# lab5.net
KiCad netlist of a schematic drawn in EAGLE
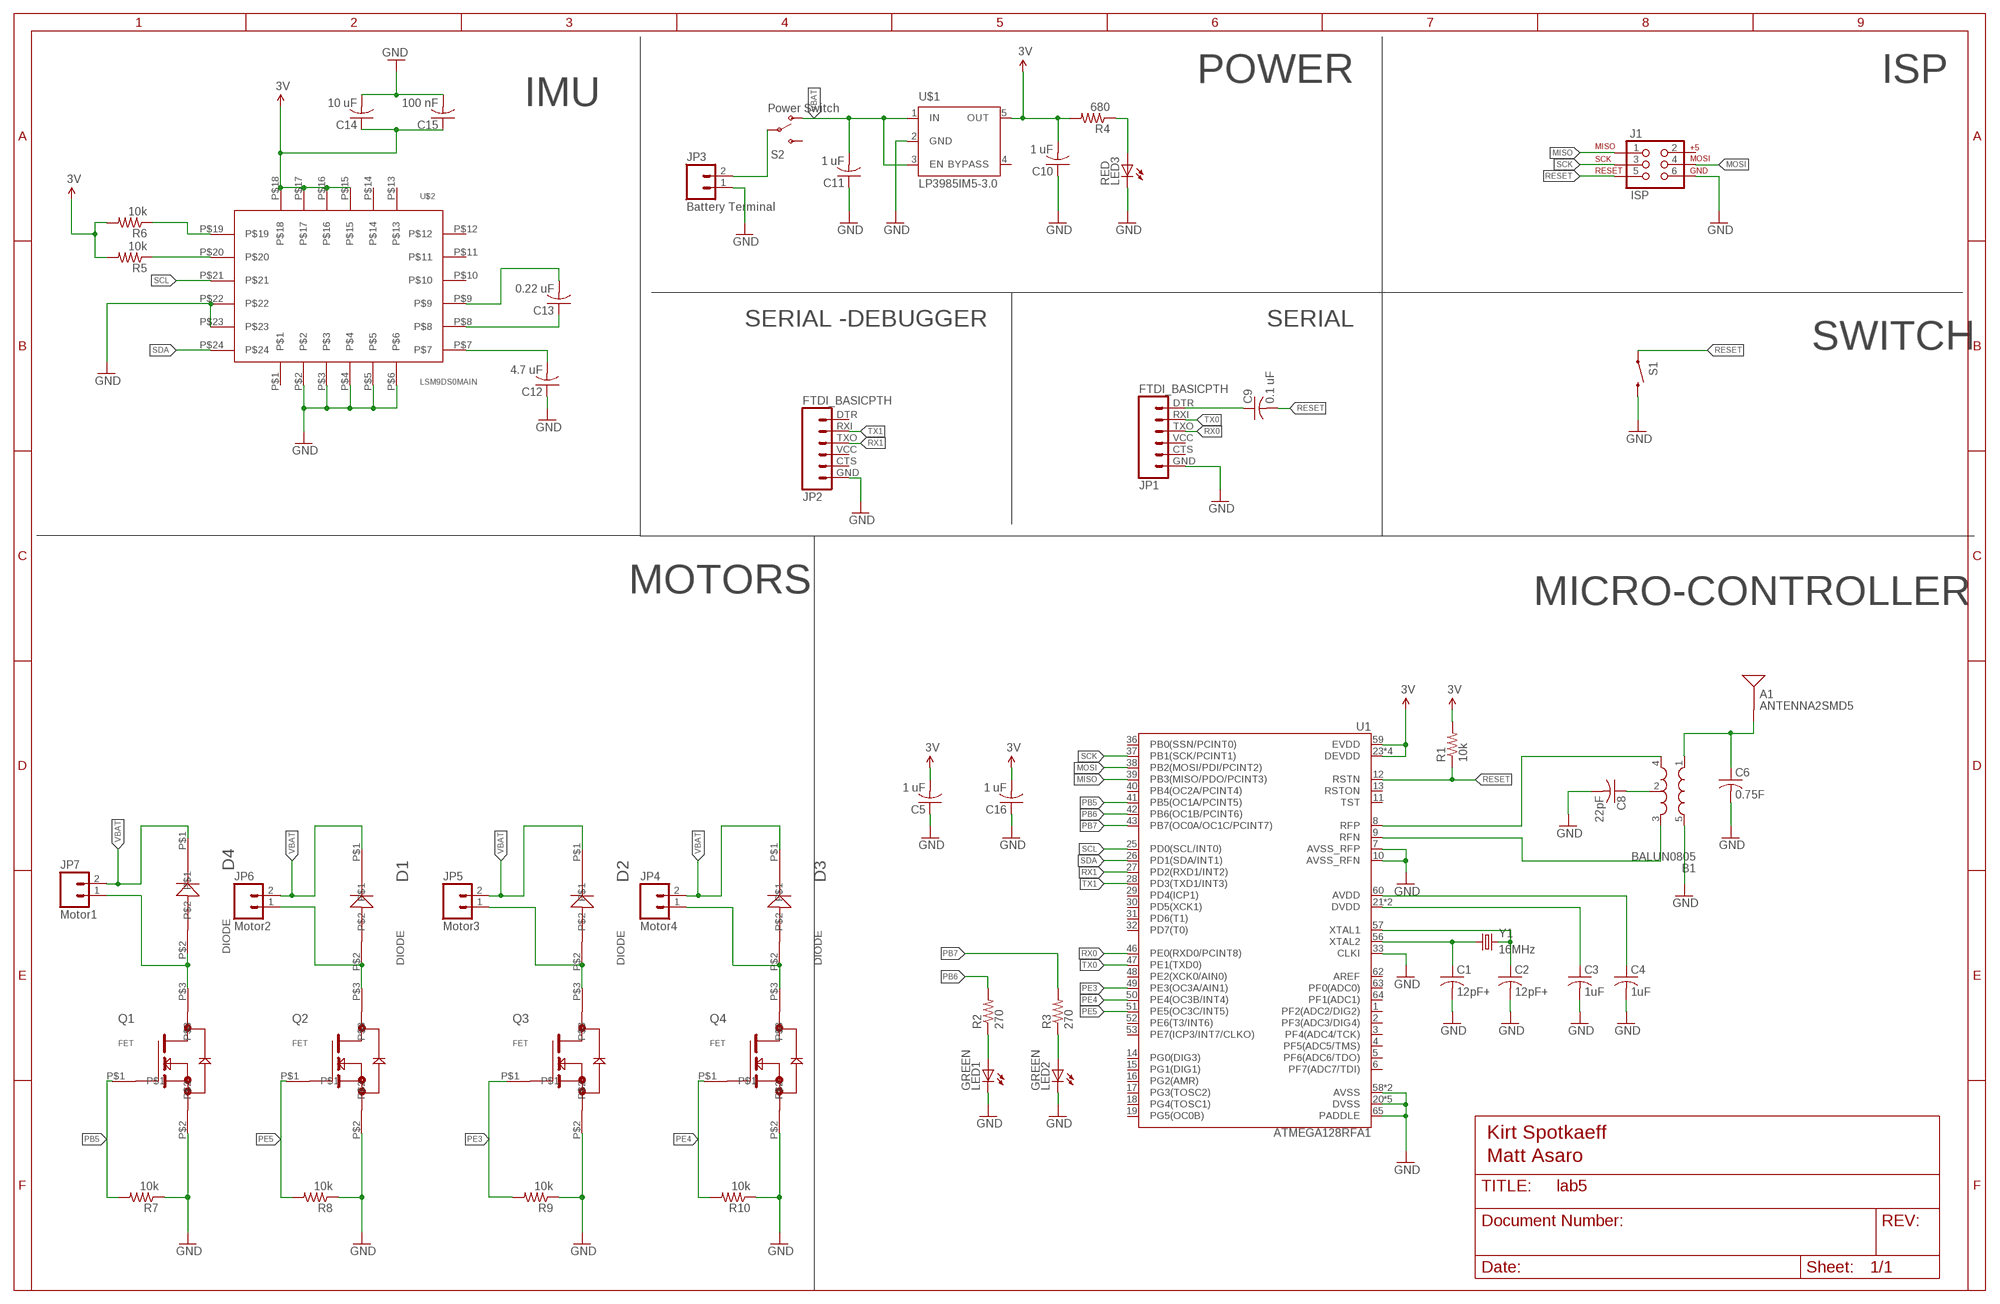
[diagram p0: schematic, sheet 1]

(export (version "E")
  (design (tool "Eeschema 10.0.6"))
  (components
    (comp (ref "A1")
      (value "ANTENNA2SMD5")
      (footprint "eagle-import:ANTENNA-CHIP5")
      (libsource (lib "eagle-import") (part "ANTENNA2SMD5"))
    )
    (comp (ref "B1")
      (value "BALUN0805")
      (footprint "eagle-import:BALUN")
      (libsource (lib "eagle-import") (part "BALUN0805"))
    )
    (comp (ref "C1")
      (value "12pF+")
      (footprint "eagle-import:C0805")
      (libsource (lib "eagle-import") (part "C-USC0805"))
    )
    (comp (ref "C2")
      (value "12pF+")
      (footprint "eagle-import:C0805")
      (libsource (lib "eagle-import") (part "C-USC0805"))
    )
    (comp (ref "C3")
      (value "1uF")
      (footprint "eagle-import:C0805")
      (libsource (lib "eagle-import") (part "C-USC0805"))
    )
    (comp (ref "C4")
      (value "1uF")
      (footprint "eagle-import:C0805")
      (libsource (lib "eagle-import") (part "C-USC0805"))
    )
    (comp (ref "C5")
      (value "1 uF")
      (footprint "eagle-import:C0805")
      (libsource (lib "eagle-import") (part "C-USC0805"))
    )
    (comp (ref "C6")
      (value "0.75F")
      (footprint "eagle-import:C0805")
      (libsource (lib "eagle-import") (part "C-USC0805"))
    )
    (comp (ref "C8")
      (value "22pF")
      (footprint "eagle-import:C0805")
      (libsource (lib "eagle-import") (part "C-USC0805"))
    )
    (comp (ref "C9")
      (value "0.1 uF")
      (footprint "eagle-import:C0805")
      (libsource (lib "eagle-import") (part "C-USC0805"))
    )
    (comp (ref "C10")
      (value "1 uF")
      (footprint "eagle-import:C0805")
      (libsource (lib "eagle-import") (part "C-USC0805"))
    )
    (comp (ref "C11")
      (value "1 uF")
      (footprint "eagle-import:C0805")
      (libsource (lib "eagle-import") (part "C-USC0805"))
    )
    (comp (ref "C12")
      (value "4.7 uF")
      (footprint "eagle-import:C0805")
      (libsource (lib "eagle-import") (part "C-USC0805"))
    )
    (comp (ref "C13")
      (value "0.22 uF")
      (footprint "eagle-import:C0805")
      (libsource (lib "eagle-import") (part "C-USC0805"))
    )
    (comp (ref "C14")
      (value "10 uF")
      (footprint "eagle-import:C0805")
      (libsource (lib "eagle-import") (part "C-USC0805"))
    )
    (comp (ref "C15")
      (value "100 nF")
      (footprint "eagle-import:C0805")
      (libsource (lib "eagle-import") (part "C-USC0805"))
    )
    (comp (ref "C16")
      (value "1 uF")
      (footprint "eagle-import:C0805")
      (libsource (lib "eagle-import") (part "C-USC0805"))
    )
    (comp (ref "D1")
      (value "DIODE")
      (footprint "eagle-import:DIODE")
      (fields (field (name "CREATOR") "Kirt Spotkaeff"))
      (libsource (lib "eagle-import") (part "DIODE"))
    )
    (comp (ref "D2")
      (value "DIODE")
      (footprint "eagle-import:DIODE")
      (fields (field (name "CREATOR") "Kirt Spotkaeff"))
      (libsource (lib "eagle-import") (part "DIODE"))
    )
    (comp (ref "D3")
      (value "DIODE")
      (footprint "eagle-import:DIODE")
      (fields (field (name "CREATOR") "Kirt Spotkaeff"))
      (libsource (lib "eagle-import") (part "DIODE"))
    )
    (comp (ref "D4")
      (value "DIODE")
      (footprint "eagle-import:DIODE")
      (fields (field (name "CREATOR") "Kirt Spotkaeff"))
      (libsource (lib "eagle-import") (part "DIODE"))
    )
    (comp (ref "J1")
      (value "ISP")
      (footprint "eagle-import:2X3-NS")
      (libsource (lib "eagle-import") (part "AVR_SPI_PRG_6NS"))
    )
    (comp (ref "JP1")
      (value "FTDI_BASICPTH")
      (footprint "eagle-import:FTDI_BASIC")
      (libsource (lib "eagle-import") (part "FTDI_BASICPTH"))
    )
    (comp (ref "JP2")
      (value "FTDI_BASICPTH")
      (footprint "eagle-import:FTDI_BASIC")
      (libsource (lib "eagle-import") (part "FTDI_BASICPTH"))
    )
    (comp (ref "JP3")
      (value "Battery Terminal")
      (footprint "eagle-import:1X02")
      (libsource (lib "eagle-import") (part "M02PTH"))
    )
    (comp (ref "JP4")
      (value "Motor4")
      (footprint "eagle-import:1X02")
      (libsource (lib "eagle-import") (part "M02PTH"))
    )
    (comp (ref "JP5")
      (value "Motor3")
      (footprint "eagle-import:1X02")
      (libsource (lib "eagle-import") (part "M02PTH"))
    )
    (comp (ref "JP6")
      (value "Motor2")
      (footprint "eagle-import:1X02")
      (libsource (lib "eagle-import") (part "M02PTH"))
    )
    (comp (ref "JP7")
      (value "Motor1")
      (footprint "eagle-import:1X02")
      (libsource (lib "eagle-import") (part "M02PTH"))
    )
    (comp (ref "LED1")
      (value "GREEN")
      (footprint "eagle-import:CHIP-LED0805")
      (libsource (lib "eagle-import") (part "LEDCHIP-LED0805"))
    )
    (comp (ref "LED2")
      (value "GREEN")
      (footprint "eagle-import:CHIP-LED0805")
      (libsource (lib "eagle-import") (part "LEDCHIP-LED0805"))
    )
    (comp (ref "LED3")
      (value "RED")
      (footprint "eagle-import:CHIP-LED0805")
      (libsource (lib "eagle-import") (part "LEDCHIP-LED0805"))
    )
    (comp (ref "Q1")
      (value "FET")
      (footprint "eagle-import:FET")
      (fields (field (name "CREATOR") "Kirt Spotkaeff"))
      (libsource (lib "eagle-import") (part "FET"))
    )
    (comp (ref "Q2")
      (value "FET")
      (footprint "eagle-import:FET")
      (fields (field (name "CREATOR") "Kirt Spotkaeff"))
      (libsource (lib "eagle-import") (part "FET"))
    )
    (comp (ref "Q3")
      (value "FET")
      (footprint "eagle-import:FET")
      (fields (field (name "CREATOR") "Kirt Spotkaeff"))
      (libsource (lib "eagle-import") (part "FET"))
    )
    (comp (ref "Q4")
      (value "FET")
      (footprint "eagle-import:FET")
      (fields (field (name "CREATOR") "Kirt Spotkaeff"))
      (libsource (lib "eagle-import") (part "FET"))
    )
    (comp (ref "R1")
      (value "10k")
      (footprint "eagle-import:R0805")
      (libsource (lib "eagle-import") (part "R-US_R0805"))
    )
    (comp (ref "R2")
      (value "270")
      (footprint "eagle-import:R0805")
      (libsource (lib "eagle-import") (part "R-US_R0805"))
    )
    (comp (ref "R3")
      (value "270")
      (footprint "eagle-import:R0805")
      (libsource (lib "eagle-import") (part "R-US_R0805"))
    )
    (comp (ref "R4")
      (value "680")
      (footprint "eagle-import:R0805")
      (libsource (lib "eagle-import") (part "R-US_R0805"))
    )
    (comp (ref "R5")
      (value "10k")
      (footprint "eagle-import:R0805")
      (libsource (lib "eagle-import") (part "R-US_R0805"))
    )
    (comp (ref "R6")
      (value "10k")
      (footprint "eagle-import:R0805")
      (libsource (lib "eagle-import") (part "R-US_R0805"))
    )
    (comp (ref "R7")
      (value "10k")
      (footprint "eagle-import:R0805")
      (libsource (lib "eagle-import") (part "R-US_R0805"))
    )
    (comp (ref "R8")
      (value "10k")
      (footprint "eagle-import:R0805")
      (libsource (lib "eagle-import") (part "R-US_R0805"))
    )
    (comp (ref "R9")
      (value "10k")
      (footprint "eagle-import:R0805")
      (libsource (lib "eagle-import") (part "R-US_R0805"))
    )
    (comp (ref "R10")
      (value "10k")
      (footprint "eagle-import:R0805")
      (libsource (lib "eagle-import") (part "R-US_R0805"))
    )
    (comp (ref "S1")
      (value "SWITCH-MOMENTARY-2SMD")
      (footprint "eagle-import:TACTILE_SWITCH_SMD")
      (libsource (lib "eagle-import") (part "SWITCH-MOMENTARY-2SMD"))
    )
    (comp (ref "S2")
      (value "Power Switch")
      (footprint "eagle-import:SWITCH-SPDT")
      (libsource (lib "eagle-import") (part "SWITCH-SPDTPTH"))
    )
    (comp (ref "U$1")
      (value "LP3985IM5-3.0")
      (footprint "eagle-import:SOT23-DBV")
      (libsource (lib "eagle-import") (part "LP3985IM5-3.0"))
    )
    (comp (ref "U$2")
      (value "LSM9DS0MAIN")
      (footprint "eagle-import:LSM9DS0")
      (libsource (lib "eagle-import") (part "LSM9DS0MAIN"))
    )
    (comp (ref "U1")
      (value "ATMEGA128RFA1")
      (footprint "eagle-import:QFN-64")
      (libsource (lib "eagle-import") (part "ATMEGA128RFA1"))
    )
    (comp (ref "Y1")
      (value "16MHz")
      (footprint "eagle-import:CRYSTAL-SMD-5X3")
      (libsource (lib "eagle-import") (part "CRYSTAL5X3"))
    )
  )
  (nets
    (net (code "1") (name "3V") (class "Default")
      (node (ref "C10") (pin "2") (pinfunction "2_2") (pintype "passive"))
      (node (ref "C14") (pin "1") (pinfunction "1_1") (pintype "passive"))
      (node (ref "C15") (pin "1") (pinfunction "1_1") (pintype "passive"))
      (node (ref "C16") (pin "2") (pinfunction "2_2") (pintype "passive"))
      (node (ref "C5") (pin "2") (pinfunction "2_2") (pintype "passive"))
      (node (ref "R1") (pin "2") (pinfunction "2_2") (pintype "passive"))
      (node (ref "R4") (pin "2") (pinfunction "2_2") (pintype "passive"))
      (node (ref "R5") (pin "2") (pinfunction "2_2") (pintype "passive"))
      (node (ref "R6") (pin "2") (pinfunction "2_2") (pintype "passive"))
      (node (ref "U$1") (pin "5") (pinfunction "OUT_5") (pintype "passive"))
      (node (ref "U$2") (pin "P$15") (pinfunction "P$15_P$15") (pintype "bidirectional"))
      (node (ref "U$2") (pin "P$16") (pinfunction "P$16_P$16") (pintype "bidirectional"))
      (node (ref "U$2") (pin "P$17") (pinfunction "P$17_P$17") (pintype "bidirectional"))
      (node (ref "U$2") (pin "P$18") (pinfunction "P$18_P$18") (pintype "bidirectional"))
      (node (ref "U1") (pin "23") (pinfunction "DEVDD_23") (pintype "bidirectional"))
      (node (ref "U1") (pin "34") (pinfunction "DEVDD_34") (pintype "bidirectional"))
      (node (ref "U1") (pin "44") (pinfunction "DEVDD_44") (pintype "bidirectional"))
      (node (ref "U1") (pin "54") (pinfunction "DEVDD_54") (pintype "bidirectional"))
      (node (ref "U1") (pin "59") (pinfunction "EVDD_59") (pintype "bidirectional"))
    )
    (net (code "2") (name "GND") (class "Default")
      (node (ref "B1") (pin "5") (pinfunction "GND_5") (pintype "bidirectional"))
      (node (ref "C1") (pin "2") (pinfunction "2_2") (pintype "passive"))
      (node (ref "C10") (pin "1") (pinfunction "1_1") (pintype "passive"))
      (node (ref "C11") (pin "1") (pinfunction "1_1") (pintype "passive"))
      (node (ref "C12") (pin "1") (pinfunction "1_1") (pintype "passive"))
      (node (ref "C14") (pin "2") (pinfunction "2_2") (pintype "passive"))
      (node (ref "C15") (pin "2") (pinfunction "2_2") (pintype "passive"))
      (node (ref "C16") (pin "1") (pinfunction "1_1") (pintype "passive"))
      (node (ref "C2") (pin "2") (pinfunction "2_2") (pintype "passive"))
      (node (ref "C3") (pin "2") (pinfunction "2_2") (pintype "passive"))
      (node (ref "C4") (pin "2") (pinfunction "2_2") (pintype "passive"))
      (node (ref "C5") (pin "1") (pinfunction "1_1") (pintype "passive"))
      (node (ref "C6") (pin "2") (pinfunction "2_2") (pintype "passive"))
      (node (ref "C8") (pin "2") (pinfunction "2_2") (pintype "passive"))
      (node (ref "J1") (pin "6") (pinfunction "6_6") (pintype "passive"))
      (node (ref "JP1") (pin "GND") (pinfunction "6_GND") (pintype "passive"))
      (node (ref "JP2") (pin "GND") (pinfunction "6_GND") (pintype "passive"))
      (node (ref "JP3") (pin "1") (pinfunction "1_1") (pintype "passive"))
      (node (ref "LED1") (pin "C") (pinfunction "C_C") (pintype "passive"))
      (node (ref "LED2") (pin "C") (pinfunction "C_C") (pintype "passive"))
      (node (ref "LED3") (pin "C") (pinfunction "C_C") (pintype "passive"))
      (node (ref "Q1") (pin "P$2") (pinfunction "P$2_P$2") (pintype "bidirectional"))
      (node (ref "Q2") (pin "P$2") (pinfunction "P$2_P$2") (pintype "bidirectional"))
      (node (ref "Q3") (pin "P$2") (pinfunction "P$2_P$2") (pintype "bidirectional"))
      (node (ref "Q4") (pin "P$2") (pinfunction "P$2_P$2") (pintype "bidirectional"))
      (node (ref "R10") (pin "1") (pinfunction "1_1") (pintype "passive"))
      (node (ref "R7") (pin "1") (pinfunction "1_1") (pintype "passive"))
      (node (ref "R8") (pin "1") (pinfunction "1_1") (pintype "passive"))
      (node (ref "R9") (pin "1") (pinfunction "1_1") (pintype "passive"))
      (node (ref "S1") (pin "3") (pinfunction "2_3") (pintype "passive"))
      (node (ref "U$1") (pin "2") (pinfunction "GND_2") (pintype "input"))
      (node (ref "U$2") (pin "P$2") (pinfunction "P$2_P$2") (pintype "bidirectional"))
      (node (ref "U$2") (pin "P$22") (pinfunction "P$22_P$22") (pintype "bidirectional"))
      (node (ref "U$2") (pin "P$23") (pinfunction "P$23_P$23") (pintype "bidirectional"))
      (node (ref "U$2") (pin "P$3") (pinfunction "P$3_P$3") (pintype "bidirectional"))
      (node (ref "U$2") (pin "P$4") (pinfunction "P$4_P$4") (pintype "bidirectional"))
      (node (ref "U$2") (pin "P$5") (pinfunction "P$5_P$5") (pintype "bidirectional"))
      (node (ref "U$2") (pin "P$6") (pinfunction "P$6_P$6") (pintype "bidirectional"))
      (node (ref "U1") (pin "10") (pinfunction "AVSS_RFN_10") (pintype "bidirectional"))
      (node (ref "U1") (pin "20") (pinfunction "DVSS_20") (pintype "bidirectional"))
      (node (ref "U1") (pin "24") (pinfunction "DVSS_24") (pintype "bidirectional"))
      (node (ref "U1") (pin "33") (pinfunction "CLKI_33") (pintype "bidirectional"))
      (node (ref "U1") (pin "35") (pinfunction "DVSS_35") (pintype "bidirectional"))
      (node (ref "U1") (pin "45") (pinfunction "DVSS_45") (pintype "bidirectional"))
      (node (ref "U1") (pin "55") (pinfunction "DVSS_55") (pintype "bidirectional"))
      (node (ref "U1") (pin "58") (pinfunction "AVSS_58") (pintype "bidirectional"))
      (node (ref "U1") (pin "61") (pinfunction "AVSS_61") (pintype "bidirectional"))
      (node (ref "U1") (pin "65") (pinfunction "PADDLE_65") (pintype "bidirectional"))
      (node (ref "U1") (pin "7") (pinfunction "AVSS_RFP_7") (pintype "bidirectional"))
    )
    (net (code "3") (name "MISO") (class "Default")
      (node (ref "J1") (pin "1") (pinfunction "1_1") (pintype "passive"))
      (node (ref "U1") (pin "39") (pinfunction "PB3(MISO/PDO/PCINT3)_39") (pintype "bidirectional"))
    )
    (net (code "4") (name "MOSI") (class "Default")
      (node (ref "J1") (pin "4") (pinfunction "4_4") (pintype "passive"))
      (node (ref "U1") (pin "38") (pinfunction "PB2(MOSI/PDI/PCINT2)_38") (pintype "bidirectional"))
    )
    (net (code "5") (name "Net-(A1-SIGNAL)") (class "Default")
      (node (ref "A1") (pin "FEED") (pinfunction "SIGNAL_FEED") (pintype "bidirectional"))
      (node (ref "B1") (pin "1") (pinfunction "IN_1") (pintype "bidirectional"))
      (node (ref "C6") (pin "1") (pinfunction "1_1") (pintype "passive"))
    )
    (net (code "6") (name "Net-(B1-GND-Pad2)") (class "Default")
      (node (ref "B1") (pin "2") (pinfunction "GND_2") (pintype "bidirectional"))
      (node (ref "C8") (pin "1") (pinfunction "1_1") (pintype "passive"))
    )
    (net (code "7") (name "Net-(B1-OUT1)") (class "Default")
      (node (ref "B1") (pin "4") (pinfunction "OUT1_4") (pintype "bidirectional"))
      (node (ref "U1") (pin "8") (pinfunction "RFP_8") (pintype "bidirectional"))
    )
    (net (code "8") (name "Net-(B1-OUT2)") (class "Default")
      (node (ref "B1") (pin "3") (pinfunction "OUT2_3") (pintype "bidirectional"))
      (node (ref "U1") (pin "9") (pinfunction "RFN_9") (pintype "bidirectional"))
    )
    (net (code "9") (name "Net-(C3-Pad1)") (class "Default")
      (node (ref "C3") (pin "1") (pinfunction "1_1") (pintype "passive"))
      (node (ref "U1") (pin "21") (pinfunction "DVDD_21") (pintype "bidirectional"))
      (node (ref "U1") (pin "22") (pinfunction "DVDD_22") (pintype "bidirectional"))
    )
    (net (code "10") (name "Net-(C12-Pad2)") (class "Default")
      (node (ref "C12") (pin "2") (pinfunction "2_2") (pintype "passive"))
      (node (ref "U$2") (pin "P$7") (pinfunction "P$7_P$7") (pintype "bidirectional"))
    )
    (net (code "11") (name "Net-(C13-Pad1)") (class "Default")
      (node (ref "C13") (pin "1") (pinfunction "1_1") (pintype "passive"))
      (node (ref "U$2") (pin "P$8") (pinfunction "P$8_P$8") (pintype "bidirectional"))
    )
    (net (code "12") (name "Net-(C13-Pad2)") (class "Default")
      (node (ref "C13") (pin "2") (pinfunction "2_2") (pintype "passive"))
      (node (ref "U$2") (pin "P$9") (pinfunction "P$9_P$9") (pintype "bidirectional"))
    )
    (net (code "13") (name "Net-(D1-PadP$2)") (class "Default")
      (node (ref "D1") (pin "P$2") (pinfunction "P$2_P$2") (pintype "bidirectional"))
      (node (ref "JP6") (pin "1") (pinfunction "1_1") (pintype "passive"))
      (node (ref "Q2") (pin "P$3") (pinfunction "P$3_P$3") (pintype "bidirectional"))
    )
    (net (code "14") (name "Net-(D2-PadP$2)") (class "Default")
      (node (ref "D2") (pin "P$2") (pinfunction "P$2_P$2") (pintype "bidirectional"))
      (node (ref "JP5") (pin "1") (pinfunction "1_1") (pintype "passive"))
      (node (ref "Q3") (pin "P$3") (pinfunction "P$3_P$3") (pintype "bidirectional"))
    )
    (net (code "15") (name "Net-(D3-PadP$2)") (class "Default")
      (node (ref "D3") (pin "P$2") (pinfunction "P$2_P$2") (pintype "bidirectional"))
      (node (ref "JP4") (pin "1") (pinfunction "1_1") (pintype "passive"))
      (node (ref "Q4") (pin "P$3") (pinfunction "P$3_P$3") (pintype "bidirectional"))
    )
    (net (code "16") (name "Net-(D4-PadP$2)") (class "Default")
      (node (ref "D4") (pin "P$2") (pinfunction "P$2_P$2") (pintype "bidirectional"))
      (node (ref "JP7") (pin "1") (pinfunction "1_1") (pintype "passive"))
      (node (ref "Q1") (pin "P$3") (pinfunction "P$3_P$3") (pintype "bidirectional"))
    )
    (net (code "17") (name "Net-(JP1-1)") (class "Default")
      (node (ref "C9") (pin "1") (pinfunction "1_1") (pintype "passive"))
      (node (ref "JP1") (pin "DTR") (pinfunction "1_DTR") (pintype "passive"))
    )
    (net (code "18") (name "Net-(LED1-PadA)") (class "Default")
      (node (ref "LED1") (pin "A") (pinfunction "A_A") (pintype "passive"))
      (node (ref "R2") (pin "1") (pinfunction "1_1") (pintype "passive"))
    )
    (net (code "19") (name "Net-(LED2-PadA)") (class "Default")
      (node (ref "LED2") (pin "A") (pinfunction "A_A") (pintype "passive"))
      (node (ref "R3") (pin "1") (pinfunction "1_1") (pintype "passive"))
    )
    (net (code "20") (name "Net-(LED3-PadA)") (class "Default")
      (node (ref "LED3") (pin "A") (pinfunction "A_A") (pintype "passive"))
      (node (ref "R4") (pin "1") (pinfunction "1_1") (pintype "passive"))
    )
    (net (code "21") (name "Net-(R5-Pad1)") (class "Default")
      (node (ref "R5") (pin "1") (pinfunction "1_1") (pintype "passive"))
      (node (ref "U$2") (pin "P$20") (pinfunction "P$20_P$20") (pintype "bidirectional"))
    )
    (net (code "22") (name "Net-(R6-Pad1)") (class "Default")
      (node (ref "R6") (pin "1") (pinfunction "1_1") (pintype "passive"))
      (node (ref "U$2") (pin "P$19") (pinfunction "P$19_P$19") (pintype "bidirectional"))
    )
    (net (code "23") (name "Net-(S2-P)") (class "Default")
      (node (ref "JP3") (pin "2") (pinfunction "2_2") (pintype "passive"))
      (node (ref "S2") (pin "2") (pinfunction "P_2") (pintype "passive"))
    )
    (net (code "24") (name "Net-(U1-AVDD)") (class "Default")
      (node (ref "C4") (pin "1") (pinfunction "1_1") (pintype "passive"))
      (node (ref "U1") (pin "60") (pinfunction "AVDD_60") (pintype "bidirectional"))
    )
    (net (code "25") (name "Net-(U1-XTAL1)") (class "Default")
      (node (ref "C2") (pin "1") (pinfunction "1_1") (pintype "passive"))
      (node (ref "U1") (pin "57") (pinfunction "XTAL1_57") (pintype "bidirectional"))
      (node (ref "Y1") (pin "3") (pinfunction "2_3") (pintype "passive"))
    )
    (net (code "26") (name "Net-(U1-XTAL2)") (class "Default")
      (node (ref "C1") (pin "1") (pinfunction "1_1") (pintype "passive"))
      (node (ref "U1") (pin "56") (pinfunction "XTAL2_56") (pintype "bidirectional"))
      (node (ref "Y1") (pin "1") (pinfunction "1_1") (pintype "passive"))
    )
    (net (code "27") (name "PB5") (class "Default")
      (node (ref "Q1") (pin "P$1") (pinfunction "P$1_P$1") (pintype "bidirectional"))
      (node (ref "R7") (pin "2") (pinfunction "2_2") (pintype "passive"))
      (node (ref "U1") (pin "41") (pinfunction "PB5(OC1A/PCINT5)_41") (pintype "bidirectional"))
    )
    (net (code "28") (name "PB6") (class "Default")
      (node (ref "R2") (pin "2") (pinfunction "2_2") (pintype "passive"))
      (node (ref "U1") (pin "42") (pinfunction "PB6(OC1B/PCINT6)_42") (pintype "bidirectional"))
    )
    (net (code "29") (name "PB7") (class "Default")
      (node (ref "R3") (pin "2") (pinfunction "2_2") (pintype "passive"))
      (node (ref "U1") (pin "43") (pinfunction "PB7(OC0A/OC1C/PCINT7)_43") (pintype "bidirectional"))
    )
    (net (code "30") (name "PE3") (class "Default")
      (node (ref "Q3") (pin "P$1") (pinfunction "P$1_P$1") (pintype "bidirectional"))
      (node (ref "R9") (pin "2") (pinfunction "2_2") (pintype "passive"))
      (node (ref "U1") (pin "49") (pinfunction "PE3(OC3A/AIN1)_49") (pintype "bidirectional"))
    )
    (net (code "31") (name "PE4") (class "Default")
      (node (ref "Q4") (pin "P$1") (pinfunction "P$1_P$1") (pintype "bidirectional"))
      (node (ref "R10") (pin "2") (pinfunction "2_2") (pintype "passive"))
      (node (ref "U1") (pin "50") (pinfunction "PE4(OC3B/INT4)_50") (pintype "bidirectional"))
    )
    (net (code "32") (name "PE5") (class "Default")
      (node (ref "Q2") (pin "P$1") (pinfunction "P$1_P$1") (pintype "bidirectional"))
      (node (ref "R8") (pin "2") (pinfunction "2_2") (pintype "passive"))
      (node (ref "U1") (pin "51") (pinfunction "PE5(OC3C/INT5)_51") (pintype "bidirectional"))
    )
    (net (code "33") (name "RESET") (class "Default")
      (node (ref "C9") (pin "2") (pinfunction "2_2") (pintype "passive"))
      (node (ref "J1") (pin "5") (pinfunction "5_5") (pintype "passive"))
      (node (ref "R1") (pin "1") (pinfunction "1_1") (pintype "passive"))
      (node (ref "S1") (pin "1") (pinfunction "1_1") (pintype "passive"))
      (node (ref "U1") (pin "12") (pinfunction "RSTN_12") (pintype "bidirectional"))
    )
    (net (code "34") (name "RX0") (class "Default")
      (node (ref "JP1") (pin "TXO") (pinfunction "3_TXO") (pintype "passive"))
      (node (ref "U1") (pin "46") (pinfunction "PE0(RXD0/PCINT8)_46") (pintype "bidirectional"))
    )
    (net (code "35") (name "RX1") (class "Default")
      (node (ref "JP2") (pin "TXO") (pinfunction "3_TXO") (pintype "passive"))
      (node (ref "U1") (pin "27") (pinfunction "PD2(RXD1/INT2)_27") (pintype "bidirectional"))
    )
    (net (code "36") (name "SCK") (class "Default")
      (node (ref "J1") (pin "3") (pinfunction "3_3") (pintype "passive"))
      (node (ref "U1") (pin "37") (pinfunction "PB1(SCK/PCINT1)_37") (pintype "bidirectional"))
    )
    (net (code "37") (name "SCL") (class "Default")
      (node (ref "U$2") (pin "P$21") (pinfunction "P$21_P$21") (pintype "bidirectional"))
      (node (ref "U1") (pin "25") (pinfunction "PD0(SCL/INT0)_25") (pintype "bidirectional"))
    )
    (net (code "38") (name "SDA") (class "Default")
      (node (ref "U$2") (pin "P$24") (pinfunction "P$24_P$24") (pintype "bidirectional"))
      (node (ref "U1") (pin "26") (pinfunction "PD1(SDA/INT1)_26") (pintype "bidirectional"))
    )
    (net (code "39") (name "TX0") (class "Default")
      (node (ref "JP1") (pin "RXI") (pinfunction "2_RXI") (pintype "passive"))
      (node (ref "U1") (pin "47") (pinfunction "PE1(TXD0)_47") (pintype "bidirectional"))
    )
    (net (code "40") (name "TX1") (class "Default")
      (node (ref "JP2") (pin "RXI") (pinfunction "2_RXI") (pintype "passive"))
      (node (ref "U1") (pin "28") (pinfunction "PD3(TXD1/INT3)_28") (pintype "bidirectional"))
    )
    (net (code "41") (name "VBAT") (class "Default")
      (node (ref "C11") (pin "2") (pinfunction "2_2") (pintype "passive"))
      (node (ref "D1") (pin "P$1") (pinfunction "P$1_P$1") (pintype "bidirectional"))
      (node (ref "D2") (pin "P$1") (pinfunction "P$1_P$1") (pintype "bidirectional"))
      (node (ref "D3") (pin "P$1") (pinfunction "P$1_P$1") (pintype "bidirectional"))
      (node (ref "D4") (pin "P$1") (pinfunction "P$1_P$1") (pintype "bidirectional"))
      (node (ref "JP4") (pin "2") (pinfunction "2_2") (pintype "passive"))
      (node (ref "JP5") (pin "2") (pinfunction "2_2") (pintype "passive"))
      (node (ref "JP6") (pin "2") (pinfunction "2_2") (pintype "passive"))
      (node (ref "JP7") (pin "2") (pinfunction "2_2") (pintype "passive"))
      (node (ref "S2") (pin "1") (pinfunction "O_1") (pintype "passive"))
      (node (ref "U$1") (pin "1") (pinfunction "IN_1") (pintype "input"))
      (node (ref "U$1") (pin "3") (pinfunction "EN_3") (pintype "input"))
    )
    (net (code "42") (name "unconnected-(J1-Pad2)") (class "Default")
      (node (ref "J1") (pin "2") (pinfunction "2_2") (pintype "passive"))
    )
    (net (code "43") (name "unconnected-(JP1-4-PadVCC)") (class "Default")
      (node (ref "JP1") (pin "VCC") (pinfunction "4_VCC") (pintype "passive"))
    )
    (net (code "44") (name "unconnected-(JP1-5-PadCTS)") (class "Default")
      (node (ref "JP1") (pin "CTS") (pinfunction "5_CTS") (pintype "passive"))
    )
    (net (code "45") (name "unconnected-(JP2-1-PadDTR)") (class "Default")
      (node (ref "JP2") (pin "DTR") (pinfunction "1_DTR") (pintype "passive"))
    )
    (net (code "46") (name "unconnected-(JP2-4-PadVCC)") (class "Default")
      (node (ref "JP2") (pin "VCC") (pinfunction "4_VCC") (pintype "passive"))
    )
    (net (code "47") (name "unconnected-(JP2-5-PadCTS)") (class "Default")
      (node (ref "JP2") (pin "CTS") (pinfunction "5_CTS") (pintype "passive"))
    )
    (net (code "48") (name "unconnected-(S2-S-Pad3)") (class "Default")
      (node (ref "S2") (pin "3") (pinfunction "S_3") (pintype "passive"))
    )
    (net (code "49") (name "unconnected-(U$1-BYPASS-Pad4)") (class "Default")
      (node (ref "U$1") (pin "4") (pinfunction "BYPASS_4") (pintype "passive"))
    )
    (net (code "50") (name "unconnected-(U$2-PadP$1)") (class "Default")
      (node (ref "U$2") (pin "P$1") (pinfunction "P$1_P$1") (pintype "bidirectional"))
    )
    (net (code "51") (name "unconnected-(U$2-PadP$10)") (class "Default")
      (node (ref "U$2") (pin "P$10") (pinfunction "P$10_P$10") (pintype "bidirectional"))
    )
    (net (code "52") (name "unconnected-(U$2-PadP$11)") (class "Default")
      (node (ref "U$2") (pin "P$11") (pinfunction "P$11_P$11") (pintype "bidirectional"))
    )
    (net (code "53") (name "unconnected-(U$2-PadP$12)") (class "Default")
      (node (ref "U$2") (pin "P$12") (pinfunction "P$12_P$12") (pintype "bidirectional"))
    )
    (net (code "54") (name "unconnected-(U$2-PadP$13)") (class "Default")
      (node (ref "U$2") (pin "P$13") (pinfunction "P$13_P$13") (pintype "bidirectional"))
    )
    (net (code "55") (name "unconnected-(U$2-PadP$14)") (class "Default")
      (node (ref "U$2") (pin "P$14") (pinfunction "P$14_P$14") (pintype "bidirectional"))
    )
    (net (code "56") (name "unconnected-(U1-AREF-Pad62)") (class "Default")
      (node (ref "U1") (pin "62") (pinfunction "AREF_62") (pintype "bidirectional"))
    )
    (net (code "57") (name "unconnected-(U1-PB0(SSN{slash}PCINT0)-Pad36)") (class "Default")
      (node (ref "U1") (pin "36") (pinfunction "PB0(SSN/PCINT0)_36") (pintype "bidirectional"))
    )
    (net (code "58") (name "unconnected-(U1-PB4(OC2A{slash}PCINT4)-Pad40)") (class "Default")
      (node (ref "U1") (pin "40") (pinfunction "PB4(OC2A/PCINT4)_40") (pintype "bidirectional"))
    )
    (net (code "59") (name "unconnected-(U1-PD4(ICP1)-Pad29)") (class "Default")
      (node (ref "U1") (pin "29") (pinfunction "PD4(ICP1)_29") (pintype "bidirectional"))
    )
    (net (code "60") (name "unconnected-(U1-PD5(XCK1)-Pad30)") (class "Default")
      (node (ref "U1") (pin "30") (pinfunction "PD5(XCK1)_30") (pintype "bidirectional"))
    )
    (net (code "61") (name "unconnected-(U1-PD6(T1)-Pad31)") (class "Default")
      (node (ref "U1") (pin "31") (pinfunction "PD6(T1)_31") (pintype "bidirectional"))
    )
    (net (code "62") (name "unconnected-(U1-PD7(T0)-Pad32)") (class "Default")
      (node (ref "U1") (pin "32") (pinfunction "PD7(T0)_32") (pintype "bidirectional"))
    )
    (net (code "63") (name "unconnected-(U1-PE2(XCK0{slash}AIN0)-Pad48)") (class "Default")
      (node (ref "U1") (pin "48") (pinfunction "PE2(XCK0/AIN0)_48") (pintype "bidirectional"))
    )
    (net (code "64") (name "unconnected-(U1-PE6(T3{slash}INT6)-Pad52)") (class "Default")
      (node (ref "U1") (pin "52") (pinfunction "PE6(T3/INT6)_52") (pintype "bidirectional"))
    )
    (net (code "65") (name "unconnected-(U1-PE7(ICP3{slash}INT7{slash}CLKO)-Pad53)") (class "Default")
      (node (ref "U1") (pin "53") (pinfunction "PE7(ICP3/INT7/CLKO)_53") (pintype "bidirectional"))
    )
    (net (code "66") (name "unconnected-(U1-PF0(ADC0)-Pad63)") (class "Default")
      (node (ref "U1") (pin "63") (pinfunction "PF0(ADC0)_63") (pintype "bidirectional"))
    )
    (net (code "67") (name "unconnected-(U1-PF1(ADC1)-Pad64)") (class "Default")
      (node (ref "U1") (pin "64") (pinfunction "PF1(ADC1)_64") (pintype "bidirectional"))
    )
    (net (code "68") (name "unconnected-(U1-PF2(ADC2{slash}DIG2)-Pad1)") (class "Default")
      (node (ref "U1") (pin "1") (pinfunction "PF2(ADC2/DIG2)_1") (pintype "bidirectional"))
    )
    (net (code "69") (name "unconnected-(U1-PF3(ADC3{slash}DIG4)-Pad2)") (class "Default")
      (node (ref "U1") (pin "2") (pinfunction "PF3(ADC3/DIG4)_2") (pintype "bidirectional"))
    )
    (net (code "70") (name "unconnected-(U1-PF4(ADC4{slash}TCK)-Pad3)") (class "Default")
      (node (ref "U1") (pin "3") (pinfunction "PF4(ADC4/TCK)_3") (pintype "bidirectional"))
    )
    (net (code "71") (name "unconnected-(U1-PF5(ADC5{slash}TMS)-Pad4)") (class "Default")
      (node (ref "U1") (pin "4") (pinfunction "PF5(ADC5/TMS)_4") (pintype "bidirectional"))
    )
    (net (code "72") (name "unconnected-(U1-PF6(ADC6{slash}TDO)-Pad5)") (class "Default")
      (node (ref "U1") (pin "5") (pinfunction "PF6(ADC6/TDO)_5") (pintype "bidirectional"))
    )
    (net (code "73") (name "unconnected-(U1-PF7(ADC7{slash}TDI)-Pad6)") (class "Default")
      (node (ref "U1") (pin "6") (pinfunction "PF7(ADC7/TDI)_6") (pintype "bidirectional"))
    )
    (net (code "74") (name "unconnected-(U1-PG0(DIG3)-Pad14)") (class "Default")
      (node (ref "U1") (pin "14") (pinfunction "PG0(DIG3)_14") (pintype "bidirectional"))
    )
    (net (code "75") (name "unconnected-(U1-PG1(DIG1)-Pad15)") (class "Default")
      (node (ref "U1") (pin "15") (pinfunction "PG1(DIG1)_15") (pintype "bidirectional"))
    )
    (net (code "76") (name "unconnected-(U1-PG2(AMR)-Pad16)") (class "Default")
      (node (ref "U1") (pin "16") (pinfunction "PG2(AMR)_16") (pintype "bidirectional"))
    )
    (net (code "77") (name "unconnected-(U1-PG3(TOSC2)-Pad17)") (class "Default")
      (node (ref "U1") (pin "17") (pinfunction "PG3(TOSC2)_17") (pintype "bidirectional"))
    )
    (net (code "78") (name "unconnected-(U1-PG4(TOSC1)-Pad18)") (class "Default")
      (node (ref "U1") (pin "18") (pinfunction "PG4(TOSC1)_18") (pintype "bidirectional"))
    )
    (net (code "79") (name "unconnected-(U1-PG5(OC0B)-Pad19)") (class "Default")
      (node (ref "U1") (pin "19") (pinfunction "PG5(OC0B)_19") (pintype "bidirectional"))
    )
    (net (code "80") (name "unconnected-(U1-RSTON-Pad13)") (class "Default")
      (node (ref "U1") (pin "13") (pinfunction "RSTON_13") (pintype "bidirectional"))
    )
    (net (code "81") (name "unconnected-(U1-TST-Pad11)") (class "Default")
      (node (ref "U1") (pin "11") (pinfunction "TST_11") (pintype "bidirectional"))
    )
  )
)
